# EMGPreamp_extRef.net
KiCad netlist of a schematic drawn in EAGLE
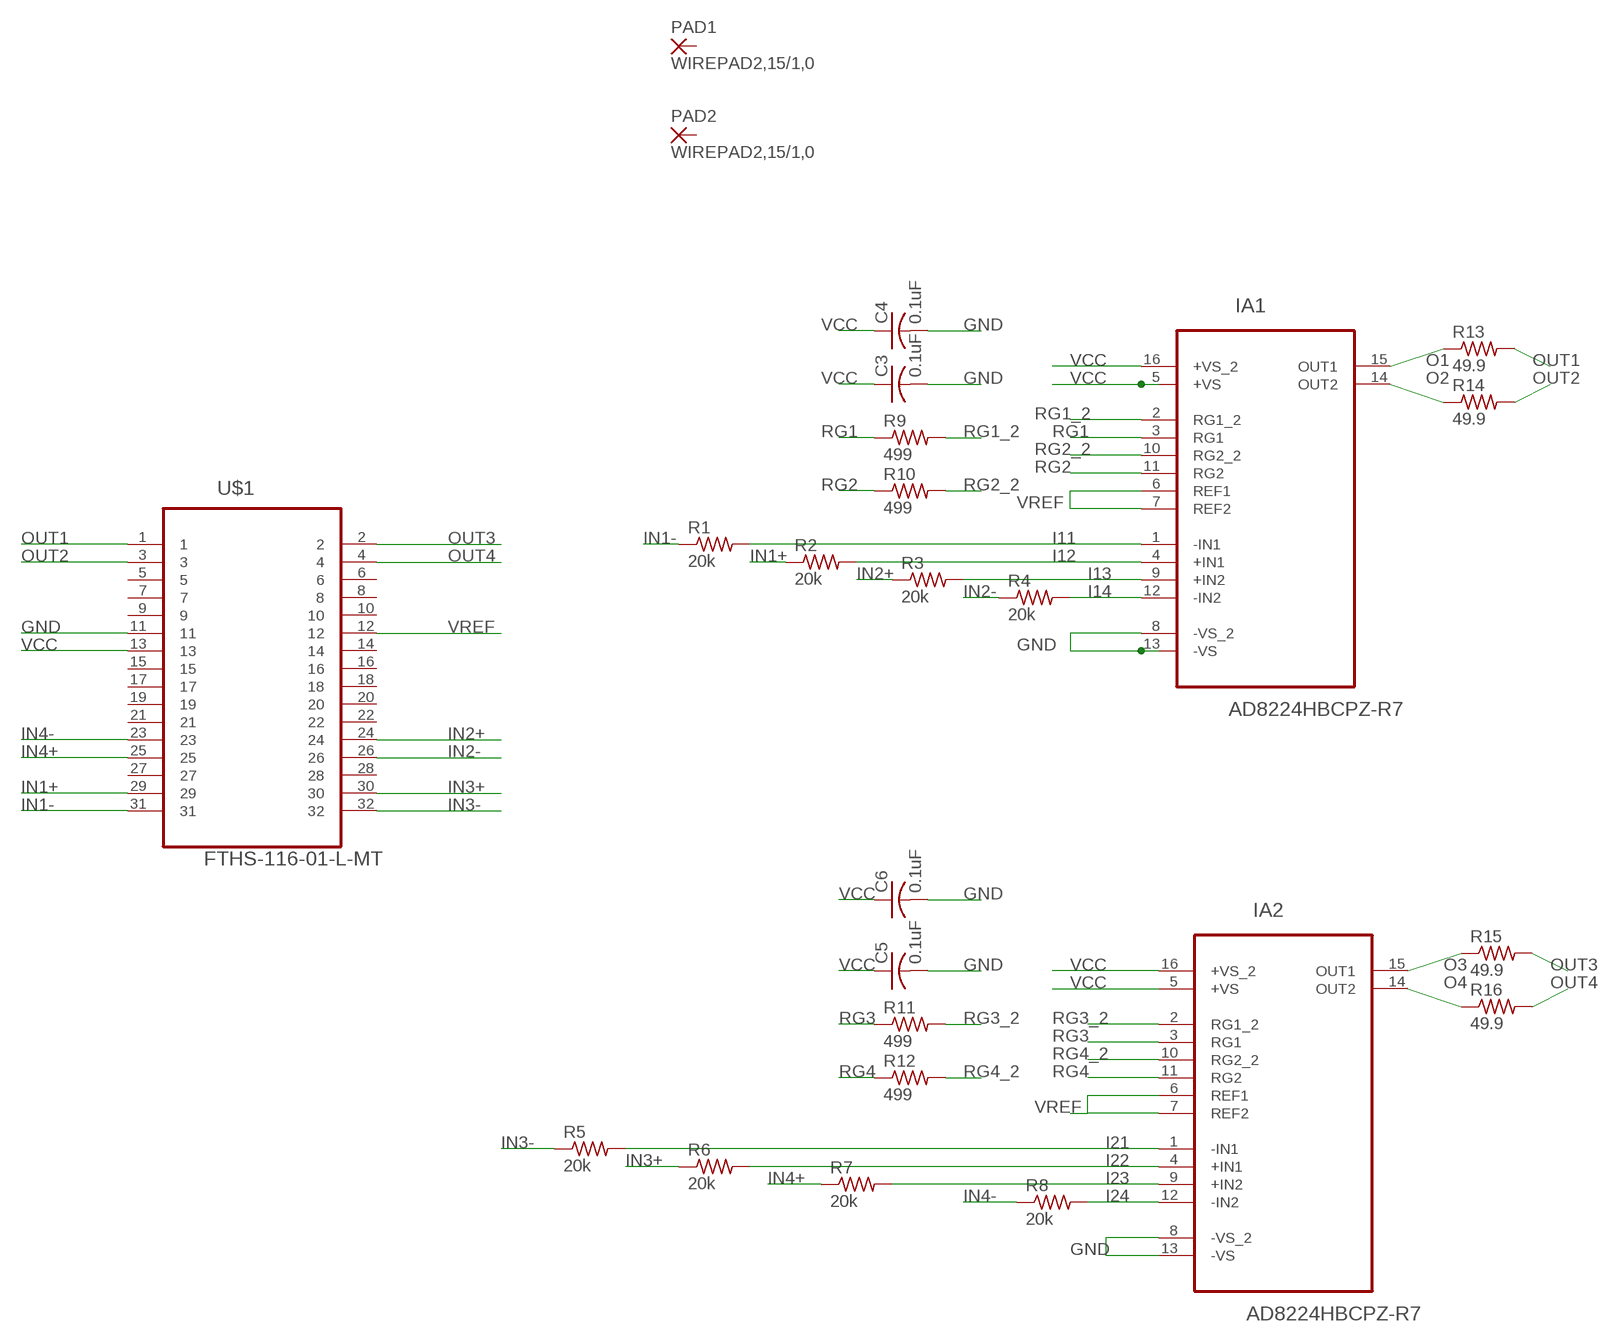
[diagram p0: schematic, sheet 1]

(export (version "E")
  (design (tool "Eeschema 10.0.6"))
  (components
    (comp (ref "C3")
      (value "0.1uF")
      (footprint "eagle-import:C0805")
      (libsource (lib "eagle-import") (part "C-USC0805"))
    )
    (comp (ref "C4")
      (value "0.1uF")
      (footprint "eagle-import:C0805")
      (libsource (lib "eagle-import") (part "C-USC0805"))
    )
    (comp (ref "C5")
      (value "0.1uF")
      (footprint "eagle-import:C0805")
      (libsource (lib "eagle-import") (part "C-USC0805"))
    )
    (comp (ref "C6")
      (value "0.1uF")
      (footprint "eagle-import:C0805")
      (libsource (lib "eagle-import") (part "C-USC0805"))
    )
    (comp (ref "IA1")
      (value "AD8224HBCPZ-R7")
      (footprint "eagle-import:QFN65P400X400X100-16N")
      (libsource (lib "eagle-import") (part "AD8224HBCPZ-R7"))
    )
    (comp (ref "IA2")
      (value "AD8224HBCPZ-R7")
      (footprint "eagle-import:QFN65P400X400X100-16N")
      (libsource (lib "eagle-import") (part "AD8224HBCPZ-R7"))
    )
    (comp (ref "PAD1")
      (value "WIREPAD2,15/1,0")
      (footprint "eagle-import:2,15_1,0")
      (libsource (lib "eagle-import") (part "WIREPAD2,15/1,0"))
    )
    (comp (ref "PAD2")
      (value "WIREPAD2,15/1,0")
      (footprint "eagle-import:2,15_1,0")
      (libsource (lib "eagle-import") (part "WIREPAD2,15/1,0"))
    )
    (comp (ref "R1")
      (value "20k")
      (footprint "eagle-import:R0805")
      (libsource (lib "eagle-import") (part "R-US_R0805"))
    )
    (comp (ref "R2")
      (value "20k")
      (footprint "eagle-import:R0805")
      (libsource (lib "eagle-import") (part "R-US_R0805"))
    )
    (comp (ref "R3")
      (value "20k")
      (footprint "eagle-import:R0805")
      (libsource (lib "eagle-import") (part "R-US_R0805"))
    )
    (comp (ref "R4")
      (value "20k")
      (footprint "eagle-import:R0805")
      (libsource (lib "eagle-import") (part "R-US_R0805"))
    )
    (comp (ref "R5")
      (value "20k")
      (footprint "eagle-import:R0805")
      (libsource (lib "eagle-import") (part "R-US_R0805"))
    )
    (comp (ref "R6")
      (value "20k")
      (footprint "eagle-import:R0805")
      (libsource (lib "eagle-import") (part "R-US_R0805"))
    )
    (comp (ref "R7")
      (value "20k")
      (footprint "eagle-import:R0805")
      (libsource (lib "eagle-import") (part "R-US_R0805"))
    )
    (comp (ref "R8")
      (value "20k")
      (footprint "eagle-import:R0805")
      (libsource (lib "eagle-import") (part "R-US_R0805"))
    )
    (comp (ref "R9")
      (value "499")
      (footprint "eagle-import:R0805")
      (libsource (lib "eagle-import") (part "R-US_R0805"))
    )
    (comp (ref "R10")
      (value "499")
      (footprint "eagle-import:R0805")
      (libsource (lib "eagle-import") (part "R-US_R0805"))
    )
    (comp (ref "R11")
      (value "499")
      (footprint "eagle-import:R0805")
      (libsource (lib "eagle-import") (part "R-US_R0805"))
    )
    (comp (ref "R12")
      (value "499")
      (footprint "eagle-import:R0805")
      (libsource (lib "eagle-import") (part "R-US_R0805"))
    )
    (comp (ref "R13")
      (value "49.9")
      (footprint "eagle-import:R0805")
      (libsource (lib "eagle-import") (part "R-US_R0805"))
    )
    (comp (ref "R14")
      (value "49.9")
      (footprint "eagle-import:R0805")
      (libsource (lib "eagle-import") (part "R-US_R0805"))
    )
    (comp (ref "R15")
      (value "49.9")
      (footprint "eagle-import:R0805")
      (libsource (lib "eagle-import") (part "R-US_R0805"))
    )
    (comp (ref "R16")
      (value "49.9")
      (footprint "eagle-import:R0805")
      (libsource (lib "eagle-import") (part "R-US_R0805"))
    )
    (comp (ref "U$1")
      (value "FTHS-116-01-L-MT")
      (footprint "eagle-import:FTSH-116-1-L-MT")
      (libsource (lib "eagle-import") (part "FTHS-116-01-L-MT"))
    )
  )
  (nets
    (net (code "1") (name "/GND") (class "Default")
      (node (ref "C3") (pin "2") (pinfunction "2_2") (pintype "passive"))
      (node (ref "C4") (pin "2") (pinfunction "2_2") (pintype "passive"))
      (node (ref "C5") (pin "2") (pinfunction "2_2") (pintype "passive"))
      (node (ref "C6") (pin "2") (pinfunction "2_2") (pintype "passive"))
      (node (ref "IA1") (pin "13") (pinfunction "-VS_13") (pintype "power_in"))
      (node (ref "IA1") (pin "8") (pinfunction "-VS_2_8") (pintype "power_in"))
      (node (ref "IA2") (pin "13") (pinfunction "-VS_13") (pintype "power_in"))
      (node (ref "IA2") (pin "8") (pinfunction "-VS_2_8") (pintype "power_in"))
      (node (ref "U$1") (pin "11") (pinfunction "11_11") (pintype "passive"))
    )
    (net (code "2") (name "/I11") (class "Default")
      (node (ref "IA1") (pin "1") (pinfunction "-IN1_1") (pintype "input"))
      (node (ref "R1") (pin "2") (pinfunction "2_2") (pintype "passive"))
    )
    (net (code "3") (name "/I12") (class "Default")
      (node (ref "IA1") (pin "4") (pinfunction "+IN1_4") (pintype "input"))
      (node (ref "R2") (pin "2") (pinfunction "2_2") (pintype "passive"))
    )
    (net (code "4") (name "/I13") (class "Default")
      (node (ref "IA1") (pin "9") (pinfunction "+IN2_9") (pintype "input"))
      (node (ref "R3") (pin "2") (pinfunction "2_2") (pintype "passive"))
    )
    (net (code "5") (name "/I14") (class "Default")
      (node (ref "IA1") (pin "12") (pinfunction "-IN2_12") (pintype "input"))
      (node (ref "R4") (pin "2") (pinfunction "2_2") (pintype "passive"))
    )
    (net (code "6") (name "/I21") (class "Default")
      (node (ref "IA2") (pin "1") (pinfunction "-IN1_1") (pintype "input"))
      (node (ref "R5") (pin "2") (pinfunction "2_2") (pintype "passive"))
    )
    (net (code "7") (name "/I22") (class "Default")
      (node (ref "IA2") (pin "4") (pinfunction "+IN1_4") (pintype "input"))
      (node (ref "R6") (pin "2") (pinfunction "2_2") (pintype "passive"))
    )
    (net (code "8") (name "/I23") (class "Default")
      (node (ref "IA2") (pin "9") (pinfunction "+IN2_9") (pintype "input"))
      (node (ref "R7") (pin "2") (pinfunction "2_2") (pintype "passive"))
    )
    (net (code "9") (name "/I24") (class "Default")
      (node (ref "IA2") (pin "12") (pinfunction "-IN2_12") (pintype "input"))
      (node (ref "R8") (pin "2") (pinfunction "2_2") (pintype "passive"))
    )
    (net (code "10") (name "/IN1+") (class "Default")
      (node (ref "R2") (pin "1") (pinfunction "1_1") (pintype "passive"))
      (node (ref "U$1") (pin "29") (pinfunction "29_29") (pintype "passive"))
    )
    (net (code "11") (name "/IN1-") (class "Default")
      (node (ref "R1") (pin "1") (pinfunction "1_1") (pintype "passive"))
      (node (ref "U$1") (pin "31") (pinfunction "31_31") (pintype "passive"))
    )
    (net (code "12") (name "/IN2+") (class "Default")
      (node (ref "R3") (pin "1") (pinfunction "1_1") (pintype "passive"))
      (node (ref "U$1") (pin "24") (pinfunction "24_24") (pintype "passive"))
    )
    (net (code "13") (name "/IN2-") (class "Default")
      (node (ref "R4") (pin "1") (pinfunction "1_1") (pintype "passive"))
      (node (ref "U$1") (pin "26") (pinfunction "26_26") (pintype "passive"))
    )
    (net (code "14") (name "/IN3+") (class "Default")
      (node (ref "R6") (pin "1") (pinfunction "1_1") (pintype "passive"))
      (node (ref "U$1") (pin "30") (pinfunction "30_30") (pintype "passive"))
    )
    (net (code "15") (name "/IN3-") (class "Default")
      (node (ref "R5") (pin "1") (pinfunction "1_1") (pintype "passive"))
      (node (ref "U$1") (pin "32") (pinfunction "32_32") (pintype "passive"))
    )
    (net (code "16") (name "/IN4+") (class "Default")
      (node (ref "R7") (pin "1") (pinfunction "1_1") (pintype "passive"))
      (node (ref "U$1") (pin "25") (pinfunction "25_25") (pintype "passive"))
    )
    (net (code "17") (name "/IN4-") (class "Default")
      (node (ref "R8") (pin "1") (pinfunction "1_1") (pintype "passive"))
      (node (ref "U$1") (pin "23") (pinfunction "23_23") (pintype "passive"))
    )
    (net (code "18") (name "/O1") (class "Default")
      (node (ref "IA1") (pin "15") (pinfunction "OUT1_15") (pintype "output"))
      (node (ref "R13") (pin "1") (pinfunction "1_1") (pintype "passive"))
    )
    (net (code "19") (name "/O2") (class "Default")
      (node (ref "IA1") (pin "14") (pinfunction "OUT2_14") (pintype "output"))
      (node (ref "R14") (pin "1") (pinfunction "1_1") (pintype "passive"))
    )
    (net (code "20") (name "/O3") (class "Default")
      (node (ref "IA2") (pin "15") (pinfunction "OUT1_15") (pintype "output"))
      (node (ref "R15") (pin "1") (pinfunction "1_1") (pintype "passive"))
    )
    (net (code "21") (name "/O4") (class "Default")
      (node (ref "IA2") (pin "14") (pinfunction "OUT2_14") (pintype "output"))
      (node (ref "R16") (pin "1") (pinfunction "1_1") (pintype "passive"))
    )
    (net (code "22") (name "/OUT1") (class "Default")
      (node (ref "R13") (pin "2") (pinfunction "2_2") (pintype "passive"))
      (node (ref "U$1") (pin "1") (pinfunction "1_1") (pintype "passive"))
    )
    (net (code "23") (name "/OUT2") (class "Default")
      (node (ref "R14") (pin "2") (pinfunction "2_2") (pintype "passive"))
      (node (ref "U$1") (pin "3") (pinfunction "3_3") (pintype "passive"))
    )
    (net (code "24") (name "/OUT3") (class "Default")
      (node (ref "R15") (pin "2") (pinfunction "2_2") (pintype "passive"))
      (node (ref "U$1") (pin "2") (pinfunction "2_2") (pintype "passive"))
    )
    (net (code "25") (name "/OUT4") (class "Default")
      (node (ref "R16") (pin "2") (pinfunction "2_2") (pintype "passive"))
      (node (ref "U$1") (pin "4") (pinfunction "4_4") (pintype "passive"))
    )
    (net (code "26") (name "/RG1") (class "Default")
      (node (ref "IA1") (pin "3") (pinfunction "RG1_3") (pintype "passive"))
      (node (ref "R9") (pin "1") (pinfunction "1_1") (pintype "passive"))
    )
    (net (code "27") (name "/RG1_2") (class "Default")
      (node (ref "IA1") (pin "2") (pinfunction "RG1_2_2") (pintype "passive"))
      (node (ref "R9") (pin "2") (pinfunction "2_2") (pintype "passive"))
    )
    (net (code "28") (name "/RG2") (class "Default")
      (node (ref "IA1") (pin "11") (pinfunction "RG2_11") (pintype "passive"))
      (node (ref "R10") (pin "1") (pinfunction "1_1") (pintype "passive"))
    )
    (net (code "29") (name "/RG2_2") (class "Default")
      (node (ref "IA1") (pin "10") (pinfunction "RG2_2_10") (pintype "passive"))
      (node (ref "R10") (pin "2") (pinfunction "2_2") (pintype "passive"))
    )
    (net (code "30") (name "/RG3") (class "Default")
      (node (ref "IA2") (pin "3") (pinfunction "RG1_3") (pintype "passive"))
      (node (ref "R11") (pin "1") (pinfunction "1_1") (pintype "passive"))
    )
    (net (code "31") (name "/RG3_2") (class "Default")
      (node (ref "IA2") (pin "2") (pinfunction "RG1_2_2") (pintype "passive"))
      (node (ref "R11") (pin "2") (pinfunction "2_2") (pintype "passive"))
    )
    (net (code "32") (name "/RG4") (class "Default")
      (node (ref "IA2") (pin "11") (pinfunction "RG2_11") (pintype "passive"))
      (node (ref "R12") (pin "1") (pinfunction "1_1") (pintype "passive"))
    )
    (net (code "33") (name "/RG4_2") (class "Default")
      (node (ref "IA2") (pin "10") (pinfunction "RG2_2_10") (pintype "passive"))
      (node (ref "R12") (pin "2") (pinfunction "2_2") (pintype "passive"))
    )
    (net (code "34") (name "/VCC") (class "Default")
      (node (ref "C3") (pin "1") (pinfunction "1_1") (pintype "passive"))
      (node (ref "C4") (pin "1") (pinfunction "1_1") (pintype "passive"))
      (node (ref "C5") (pin "1") (pinfunction "1_1") (pintype "passive"))
      (node (ref "C6") (pin "1") (pinfunction "1_1") (pintype "passive"))
      (node (ref "IA1") (pin "16") (pinfunction "+VS_2_16") (pintype "power_in"))
      (node (ref "IA1") (pin "5") (pinfunction "+VS_5") (pintype "power_in"))
      (node (ref "IA2") (pin "16") (pinfunction "+VS_2_16") (pintype "power_in"))
      (node (ref "IA2") (pin "5") (pinfunction "+VS_5") (pintype "power_in"))
      (node (ref "U$1") (pin "13") (pinfunction "13_13") (pintype "passive"))
    )
    (net (code "35") (name "/VREF") (class "Default")
      (node (ref "IA1") (pin "6") (pinfunction "REF1_6") (pintype "input"))
      (node (ref "IA1") (pin "7") (pinfunction "REF2_7") (pintype "input"))
      (node (ref "IA2") (pin "6") (pinfunction "REF1_6") (pintype "input"))
      (node (ref "IA2") (pin "7") (pinfunction "REF2_7") (pintype "input"))
      (node (ref "U$1") (pin "12") (pinfunction "12_12") (pintype "passive"))
    )
    (net (code "36") (name "unconnected-(PAD1-P-Pad1)") (class "Default")
      (node (ref "PAD1") (pin "1") (pinfunction "P_1") (pintype "passive"))
    )
    (net (code "37") (name "unconnected-(PAD2-P-Pad1)") (class "Default")
      (node (ref "PAD2") (pin "1") (pinfunction "P_1") (pintype "passive"))
    )
    (net (code "38") (name "unconnected-(U$1-Pad5)") (class "Default")
      (node (ref "U$1") (pin "5") (pinfunction "5_5") (pintype "passive"))
    )
    (net (code "39") (name "unconnected-(U$1-Pad6)") (class "Default")
      (node (ref "U$1") (pin "6") (pinfunction "6_6") (pintype "passive"))
    )
    (net (code "40") (name "unconnected-(U$1-Pad7)") (class "Default")
      (node (ref "U$1") (pin "7") (pinfunction "7_7") (pintype "passive"))
    )
    (net (code "41") (name "unconnected-(U$1-Pad8)") (class "Default")
      (node (ref "U$1") (pin "8") (pinfunction "8_8") (pintype "passive"))
    )
    (net (code "42") (name "unconnected-(U$1-Pad9)") (class "Default")
      (node (ref "U$1") (pin "9") (pinfunction "9_9") (pintype "passive"))
    )
    (net (code "43") (name "unconnected-(U$1-Pad10)") (class "Default")
      (node (ref "U$1") (pin "10") (pinfunction "10_10") (pintype "passive"))
    )
    (net (code "44") (name "unconnected-(U$1-Pad14)") (class "Default")
      (node (ref "U$1") (pin "14") (pinfunction "14_14") (pintype "passive"))
    )
    (net (code "45") (name "unconnected-(U$1-Pad15)") (class "Default")
      (node (ref "U$1") (pin "15") (pinfunction "15_15") (pintype "passive"))
    )
    (net (code "46") (name "unconnected-(U$1-Pad16)") (class "Default")
      (node (ref "U$1") (pin "16") (pinfunction "16_16") (pintype "passive"))
    )
    (net (code "47") (name "unconnected-(U$1-Pad17)") (class "Default")
      (node (ref "U$1") (pin "17") (pinfunction "17_17") (pintype "passive"))
    )
    (net (code "48") (name "unconnected-(U$1-Pad18)") (class "Default")
      (node (ref "U$1") (pin "18") (pinfunction "18_18") (pintype "passive"))
    )
    (net (code "49") (name "unconnected-(U$1-Pad19)") (class "Default")
      (node (ref "U$1") (pin "19") (pinfunction "19_19") (pintype "passive"))
    )
    (net (code "50") (name "unconnected-(U$1-Pad20)") (class "Default")
      (node (ref "U$1") (pin "20") (pinfunction "20_20") (pintype "passive"))
    )
    (net (code "51") (name "unconnected-(U$1-Pad21)") (class "Default")
      (node (ref "U$1") (pin "21") (pinfunction "21_21") (pintype "passive"))
    )
    (net (code "52") (name "unconnected-(U$1-Pad22)") (class "Default")
      (node (ref "U$1") (pin "22") (pinfunction "22_22") (pintype "passive"))
    )
    (net (code "53") (name "unconnected-(U$1-Pad27)") (class "Default")
      (node (ref "U$1") (pin "27") (pinfunction "27_27") (pintype "passive"))
    )
    (net (code "54") (name "unconnected-(U$1-Pad28)") (class "Default")
      (node (ref "U$1") (pin "28") (pinfunction "28_28") (pintype "passive"))
    )
  )
)
